# murdock_top_v2.net
KiCad netlist of a schematic drawn in EAGLE
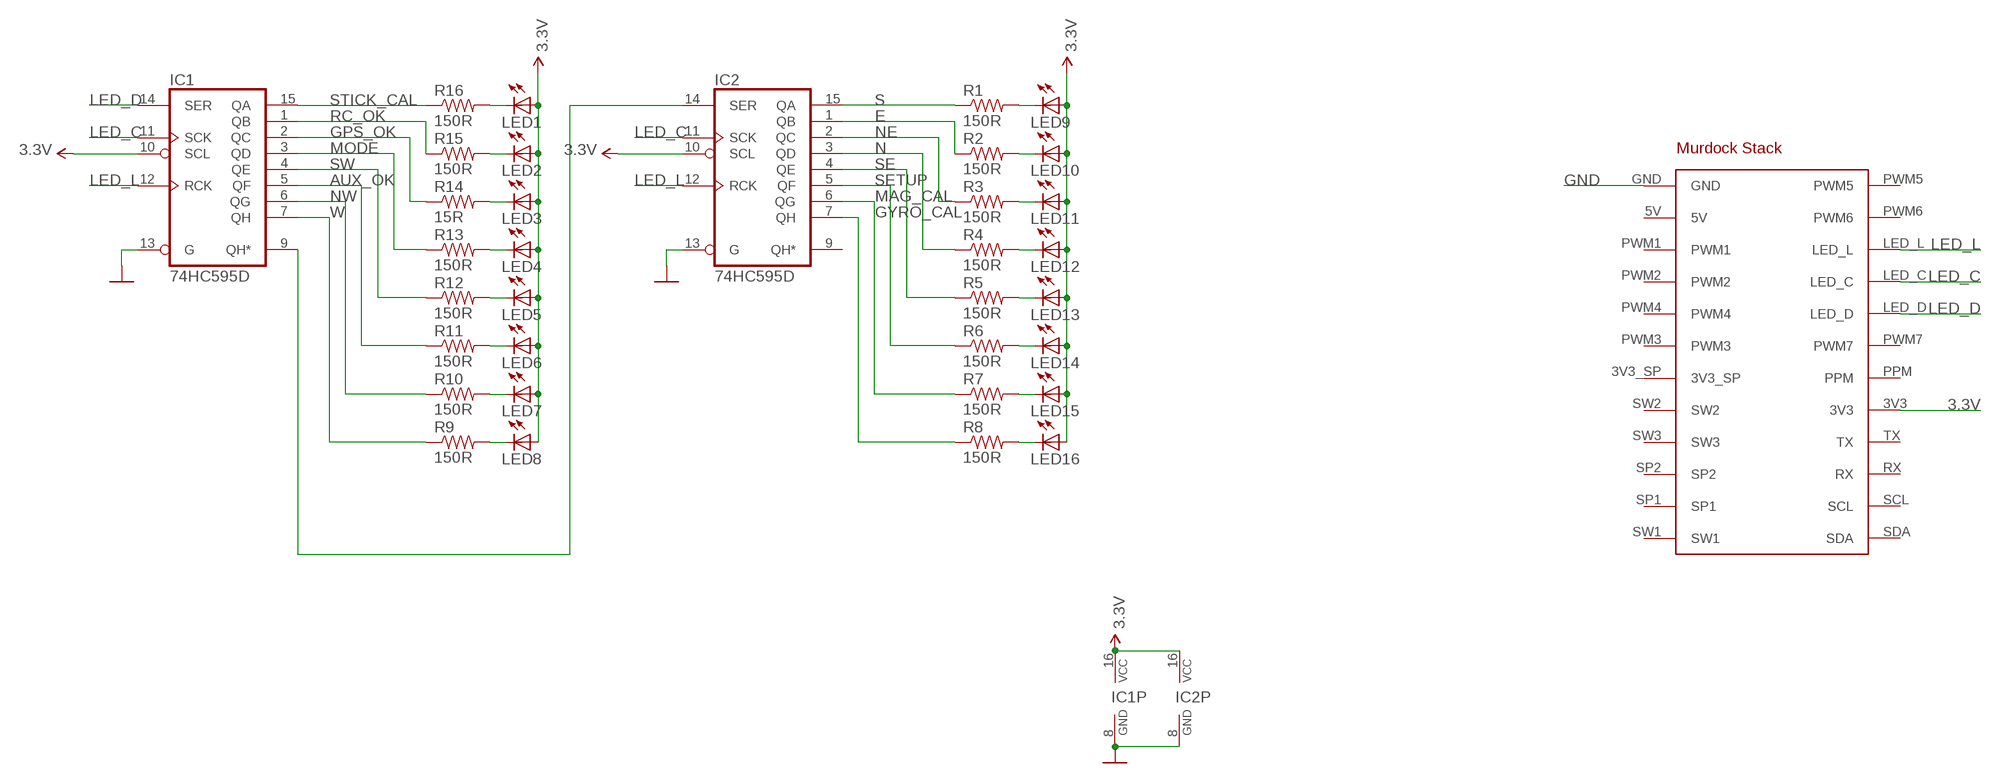
[diagram p0: schematic, sheet 1]

(export (version "E")
  (design (tool "Eeschema 10.0.6"))
  (components
    (comp (ref "IC1")
      (value "74HC595D")
      (footprint "eagle-import:SO16")
      (libsource (lib "eagle-import") (part "74595DHC"))
    )
    (comp (ref "IC2")
      (value "74HC595D")
      (footprint "eagle-import:SO16")
      (libsource (lib "eagle-import") (part "74595DHC"))
    )
    (comp (ref "LED1")
      (value "LGM47K")
      (footprint "eagle-import:LGM47K")
      (libsource (lib "eagle-import") (part "LGM47K"))
    )
    (comp (ref "LED2")
      (value "LGM47K")
      (footprint "eagle-import:LGM47K")
      (libsource (lib "eagle-import") (part "LGM47K"))
    )
    (comp (ref "LED3")
      (value "LGM47K")
      (footprint "eagle-import:LGM47K")
      (libsource (lib "eagle-import") (part "LGM47K"))
    )
    (comp (ref "LED4")
      (value "LGM47K")
      (footprint "eagle-import:LGM47K")
      (libsource (lib "eagle-import") (part "LGM47K"))
    )
    (comp (ref "LED5")
      (value "LGM47K")
      (footprint "eagle-import:LGM47K")
      (libsource (lib "eagle-import") (part "LGM47K"))
    )
    (comp (ref "LED6")
      (value "LGM47K")
      (footprint "eagle-import:LGM47K")
      (libsource (lib "eagle-import") (part "LGM47K"))
    )
    (comp (ref "LED7")
      (value "LGM47K")
      (footprint "eagle-import:LGM47K")
      (libsource (lib "eagle-import") (part "LGM47K"))
    )
    (comp (ref "LED8")
      (value "LGM47K")
      (footprint "eagle-import:LGM47K")
      (libsource (lib "eagle-import") (part "LGM47K"))
    )
    (comp (ref "LED9")
      (value "LGM47K")
      (footprint "eagle-import:LGM47K")
      (libsource (lib "eagle-import") (part "LGM47K"))
    )
    (comp (ref "LED10")
      (value "LGM47K")
      (footprint "eagle-import:LGM47K")
      (libsource (lib "eagle-import") (part "LGM47K"))
    )
    (comp (ref "LED11")
      (value "LGM47K")
      (footprint "eagle-import:LGM47K")
      (libsource (lib "eagle-import") (part "LGM47K"))
    )
    (comp (ref "LED12")
      (value "LGM47K")
      (footprint "eagle-import:LGM47K")
      (libsource (lib "eagle-import") (part "LGM47K"))
    )
    (comp (ref "LED13")
      (value "LGM47K")
      (footprint "eagle-import:LGM47K")
      (libsource (lib "eagle-import") (part "LGM47K"))
    )
    (comp (ref "LED14")
      (value "LGM47K")
      (footprint "eagle-import:LGM47K")
      (libsource (lib "eagle-import") (part "LGM47K"))
    )
    (comp (ref "LED15")
      (value "LGM47K")
      (footprint "eagle-import:LGM47K")
      (libsource (lib "eagle-import") (part "LGM47K"))
    )
    (comp (ref "LED16")
      (value "LGM47K")
      (footprint "eagle-import:LGM47K")
      (libsource (lib "eagle-import") (part "LGM47K"))
    )
    (comp (ref "R1")
      (value "150R")
      (footprint "eagle-import:0402-RES")
      (libsource (lib "eagle-import") (part "RESISTOR0402-RES"))
    )
    (comp (ref "R2")
      (value "150R")
      (footprint "eagle-import:0402-RES")
      (libsource (lib "eagle-import") (part "RESISTOR0402-RES"))
    )
    (comp (ref "R3")
      (value "150R")
      (footprint "eagle-import:0402-RES")
      (libsource (lib "eagle-import") (part "RESISTOR0402-RES"))
    )
    (comp (ref "R4")
      (value "150R")
      (footprint "eagle-import:0402-RES")
      (libsource (lib "eagle-import") (part "RESISTOR0402-RES"))
    )
    (comp (ref "R5")
      (value "150R")
      (footprint "eagle-import:0402-RES")
      (libsource (lib "eagle-import") (part "RESISTOR0402-RES"))
    )
    (comp (ref "R6")
      (value "150R")
      (footprint "eagle-import:0402-RES")
      (libsource (lib "eagle-import") (part "RESISTOR0402-RES"))
    )
    (comp (ref "R7")
      (value "150R")
      (footprint "eagle-import:0402-RES")
      (libsource (lib "eagle-import") (part "RESISTOR0402-RES"))
    )
    (comp (ref "R8")
      (value "150R")
      (footprint "eagle-import:0402-RES")
      (libsource (lib "eagle-import") (part "RESISTOR0402-RES"))
    )
    (comp (ref "R9")
      (value "150R")
      (footprint "eagle-import:0402-RES")
      (libsource (lib "eagle-import") (part "RESISTOR0402-RES"))
    )
    (comp (ref "R10")
      (value "150R")
      (footprint "eagle-import:0402-RES")
      (libsource (lib "eagle-import") (part "RESISTOR0402-RES"))
    )
    (comp (ref "R11")
      (value "150R")
      (footprint "eagle-import:0402-RES")
      (libsource (lib "eagle-import") (part "RESISTOR0402-RES"))
    )
    (comp (ref "R12")
      (value "150R")
      (footprint "eagle-import:0402-RES")
      (libsource (lib "eagle-import") (part "RESISTOR0402-RES"))
    )
    (comp (ref "R13")
      (value "150R")
      (footprint "eagle-import:0402-RES")
      (libsource (lib "eagle-import") (part "RESISTOR0402-RES"))
    )
    (comp (ref "R14")
      (value "15R")
      (footprint "eagle-import:0402-RES")
      (libsource (lib "eagle-import") (part "RESISTOR0402-RES"))
    )
    (comp (ref "R15")
      (value "150R")
      (footprint "eagle-import:0402-RES")
      (libsource (lib "eagle-import") (part "RESISTOR0402-RES"))
    )
    (comp (ref "R16")
      (value "150R")
      (footprint "eagle-import:0402-RES")
      (libsource (lib "eagle-import") (part "RESISTOR0402-RES"))
    )
    (comp (ref "X1")
      (value "MURDOCK_STACK")
      (footprint "eagle-import:MURDOCK_STACK")
      (libsource (lib "eagle-import") (part "MURDOCK_STACK"))
    )
  )
  (nets
    (net (code "1") (name "/AUX_OK") (class "Default")
      (node (ref "IC1") (pin "5") (pinfunction "QF_5") (pintype "tri_state"))
      (node (ref "R11") (pin "1") (pinfunction "1_1") (pintype "passive"))
    )
    (net (code "2") (name "/E") (class "Default")
      (node (ref "IC2") (pin "1") (pinfunction "QB_1") (pintype "tri_state"))
      (node (ref "R2") (pin "1") (pinfunction "1_1") (pintype "passive"))
    )
    (net (code "3") (name "/GPS_OK") (class "Default")
      (node (ref "IC1") (pin "2") (pinfunction "QC_2") (pintype "tri_state"))
      (node (ref "R14") (pin "1") (pinfunction "1_1") (pintype "passive"))
    )
    (net (code "4") (name "/GYRO_CAL") (class "Default")
      (node (ref "IC2") (pin "7") (pinfunction "QH_7") (pintype "tri_state"))
      (node (ref "R8") (pin "1") (pinfunction "1_1") (pintype "passive"))
    )
    (net (code "5") (name "/LED_C") (class "Default")
      (node (ref "IC1") (pin "11") (pinfunction "SCK_11") (pintype "input"))
      (node (ref "IC2") (pin "11") (pinfunction "SCK_11") (pintype "input"))
      (node (ref "X1") (pin "LED_C") (pinfunction "LED_C_LED_C") (pintype "bidirectional"))
    )
    (net (code "6") (name "/LED_D") (class "Default")
      (node (ref "IC1") (pin "14") (pinfunction "SER_14") (pintype "input"))
      (node (ref "X1") (pin "LED_D") (pinfunction "LED_D_LED_D") (pintype "bidirectional"))
    )
    (net (code "7") (name "/LED_L") (class "Default")
      (node (ref "IC1") (pin "12") (pinfunction "RCK_12") (pintype "input"))
      (node (ref "IC2") (pin "12") (pinfunction "RCK_12") (pintype "input"))
      (node (ref "X1") (pin "LED_L") (pinfunction "LED_L_LED_L") (pintype "bidirectional"))
    )
    (net (code "8") (name "/MAG_CAL") (class "Default")
      (node (ref "IC2") (pin "6") (pinfunction "QG_6") (pintype "tri_state"))
      (node (ref "R7") (pin "1") (pinfunction "1_1") (pintype "passive"))
    )
    (net (code "9") (name "/MODE") (class "Default")
      (node (ref "IC1") (pin "3") (pinfunction "QD_3") (pintype "tri_state"))
      (node (ref "R13") (pin "1") (pinfunction "1_1") (pintype "passive"))
    )
    (net (code "10") (name "/N") (class "Default")
      (node (ref "IC2") (pin "3") (pinfunction "QD_3") (pintype "tri_state"))
      (node (ref "R4") (pin "1") (pinfunction "1_1") (pintype "passive"))
    )
    (net (code "11") (name "/NE") (class "Default")
      (node (ref "IC2") (pin "2") (pinfunction "QC_2") (pintype "tri_state"))
      (node (ref "R3") (pin "1") (pinfunction "1_1") (pintype "passive"))
    )
    (net (code "12") (name "/NW") (class "Default")
      (node (ref "IC1") (pin "6") (pinfunction "QG_6") (pintype "tri_state"))
      (node (ref "R10") (pin "1") (pinfunction "1_1") (pintype "passive"))
    )
    (net (code "13") (name "/RC_OK") (class "Default")
      (node (ref "IC1") (pin "1") (pinfunction "QB_1") (pintype "tri_state"))
      (node (ref "R15") (pin "1") (pinfunction "1_1") (pintype "passive"))
    )
    (net (code "14") (name "/S") (class "Default")
      (node (ref "IC2") (pin "15") (pinfunction "QA_15") (pintype "tri_state"))
      (node (ref "R1") (pin "1") (pinfunction "1_1") (pintype "passive"))
    )
    (net (code "15") (name "/SE") (class "Default")
      (node (ref "IC2") (pin "4") (pinfunction "QE_4") (pintype "tri_state"))
      (node (ref "R5") (pin "1") (pinfunction "1_1") (pintype "passive"))
    )
    (net (code "16") (name "/SETUP") (class "Default")
      (node (ref "IC2") (pin "5") (pinfunction "QF_5") (pintype "tri_state"))
      (node (ref "R6") (pin "1") (pinfunction "1_1") (pintype "passive"))
    )
    (net (code "17") (name "/STICK_CAL") (class "Default")
      (node (ref "IC1") (pin "15") (pinfunction "QA_15") (pintype "tri_state"))
      (node (ref "R16") (pin "1") (pinfunction "1_1") (pintype "passive"))
    )
    (net (code "18") (name "/SW") (class "Default")
      (node (ref "IC1") (pin "4") (pinfunction "QE_4") (pintype "tri_state"))
      (node (ref "R12") (pin "1") (pinfunction "1_1") (pintype "passive"))
    )
    (net (code "19") (name "/W") (class "Default")
      (node (ref "IC1") (pin "7") (pinfunction "QH_7") (pintype "tri_state"))
      (node (ref "R9") (pin "1") (pinfunction "1_1") (pintype "passive"))
    )
    (net (code "20") (name "3.3V") (class "Default")
      (node (ref "IC1") (pin "10") (pinfunction "SCL_10") (pintype "input"))
      (node (ref "IC1") (pin "16") (pinfunction "VCC_16") (pintype "power_in"))
      (node (ref "IC2") (pin "10") (pinfunction "SCL_10") (pintype "input"))
      (node (ref "IC2") (pin "16") (pinfunction "VCC_16") (pintype "power_in"))
      (node (ref "LED1") (pin "A") (pinfunction "A_A") (pintype "passive"))
      (node (ref "LED10") (pin "A") (pinfunction "A_A") (pintype "passive"))
      (node (ref "LED11") (pin "A") (pinfunction "A_A") (pintype "passive"))
      (node (ref "LED12") (pin "A") (pinfunction "A_A") (pintype "passive"))
      (node (ref "LED13") (pin "A") (pinfunction "A_A") (pintype "passive"))
      (node (ref "LED14") (pin "A") (pinfunction "A_A") (pintype "passive"))
      (node (ref "LED15") (pin "A") (pinfunction "A_A") (pintype "passive"))
      (node (ref "LED16") (pin "A") (pinfunction "A_A") (pintype "passive"))
      (node (ref "LED2") (pin "A") (pinfunction "A_A") (pintype "passive"))
      (node (ref "LED3") (pin "A") (pinfunction "A_A") (pintype "passive"))
      (node (ref "LED4") (pin "A") (pinfunction "A_A") (pintype "passive"))
      (node (ref "LED5") (pin "A") (pinfunction "A_A") (pintype "passive"))
      (node (ref "LED6") (pin "A") (pinfunction "A_A") (pintype "passive"))
      (node (ref "LED7") (pin "A") (pinfunction "A_A") (pintype "passive"))
      (node (ref "LED8") (pin "A") (pinfunction "A_A") (pintype "passive"))
      (node (ref "LED9") (pin "A") (pinfunction "A_A") (pintype "passive"))
      (node (ref "X1") (pin "3V3") (pinfunction "3V3_3V3") (pintype "bidirectional"))
    )
    (net (code "21") (name "GND") (class "Default")
      (node (ref "IC1") (pin "13") (pinfunction "G_13") (pintype "input"))
      (node (ref "IC1") (pin "8") (pinfunction "GND_8") (pintype "power_in"))
      (node (ref "IC2") (pin "13") (pinfunction "G_13") (pintype "input"))
      (node (ref "IC2") (pin "8") (pinfunction "GND_8") (pintype "power_in"))
      (node (ref "X1") (pin "GND") (pinfunction "GND_GND") (pintype "bidirectional"))
    )
    (net (code "22") (name "Net-(IC1A-QH*)") (class "Default")
      (node (ref "IC1") (pin "9") (pinfunction "QH*_9") (pintype "tri_state"))
      (node (ref "IC2") (pin "14") (pinfunction "SER_14") (pintype "input"))
    )
    (net (code "23") (name "Net-(LED1-C)") (class "Default")
      (node (ref "LED1") (pin "K") (pinfunction "C_K") (pintype "passive"))
      (node (ref "R16") (pin "2") (pinfunction "2_2") (pintype "passive"))
    )
    (net (code "24") (name "Net-(LED2-C)") (class "Default")
      (node (ref "LED2") (pin "K") (pinfunction "C_K") (pintype "passive"))
      (node (ref "R15") (pin "2") (pinfunction "2_2") (pintype "passive"))
    )
    (net (code "25") (name "Net-(LED3-C)") (class "Default")
      (node (ref "LED3") (pin "K") (pinfunction "C_K") (pintype "passive"))
      (node (ref "R14") (pin "2") (pinfunction "2_2") (pintype "passive"))
    )
    (net (code "26") (name "Net-(LED4-C)") (class "Default")
      (node (ref "LED4") (pin "K") (pinfunction "C_K") (pintype "passive"))
      (node (ref "R13") (pin "2") (pinfunction "2_2") (pintype "passive"))
    )
    (net (code "27") (name "Net-(LED5-C)") (class "Default")
      (node (ref "LED5") (pin "K") (pinfunction "C_K") (pintype "passive"))
      (node (ref "R12") (pin "2") (pinfunction "2_2") (pintype "passive"))
    )
    (net (code "28") (name "Net-(LED6-C)") (class "Default")
      (node (ref "LED6") (pin "K") (pinfunction "C_K") (pintype "passive"))
      (node (ref "R11") (pin "2") (pinfunction "2_2") (pintype "passive"))
    )
    (net (code "29") (name "Net-(LED7-C)") (class "Default")
      (node (ref "LED7") (pin "K") (pinfunction "C_K") (pintype "passive"))
      (node (ref "R10") (pin "2") (pinfunction "2_2") (pintype "passive"))
    )
    (net (code "30") (name "Net-(LED8-C)") (class "Default")
      (node (ref "LED8") (pin "K") (pinfunction "C_K") (pintype "passive"))
      (node (ref "R9") (pin "2") (pinfunction "2_2") (pintype "passive"))
    )
    (net (code "31") (name "Net-(LED9-C)") (class "Default")
      (node (ref "LED9") (pin "K") (pinfunction "C_K") (pintype "passive"))
      (node (ref "R1") (pin "2") (pinfunction "2_2") (pintype "passive"))
    )
    (net (code "32") (name "Net-(LED10-C)") (class "Default")
      (node (ref "LED10") (pin "K") (pinfunction "C_K") (pintype "passive"))
      (node (ref "R2") (pin "2") (pinfunction "2_2") (pintype "passive"))
    )
    (net (code "33") (name "Net-(LED11-C)") (class "Default")
      (node (ref "LED11") (pin "K") (pinfunction "C_K") (pintype "passive"))
      (node (ref "R3") (pin "2") (pinfunction "2_2") (pintype "passive"))
    )
    (net (code "34") (name "Net-(LED12-C)") (class "Default")
      (node (ref "LED12") (pin "K") (pinfunction "C_K") (pintype "passive"))
      (node (ref "R4") (pin "2") (pinfunction "2_2") (pintype "passive"))
    )
    (net (code "35") (name "Net-(LED13-C)") (class "Default")
      (node (ref "LED13") (pin "K") (pinfunction "C_K") (pintype "passive"))
      (node (ref "R5") (pin "2") (pinfunction "2_2") (pintype "passive"))
    )
    (net (code "36") (name "Net-(LED14-C)") (class "Default")
      (node (ref "LED14") (pin "K") (pinfunction "C_K") (pintype "passive"))
      (node (ref "R6") (pin "2") (pinfunction "2_2") (pintype "passive"))
    )
    (net (code "37") (name "Net-(LED15-C)") (class "Default")
      (node (ref "LED15") (pin "K") (pinfunction "C_K") (pintype "passive"))
      (node (ref "R7") (pin "2") (pinfunction "2_2") (pintype "passive"))
    )
    (net (code "38") (name "Net-(LED16-C)") (class "Default")
      (node (ref "LED16") (pin "K") (pinfunction "C_K") (pintype "passive"))
      (node (ref "R8") (pin "2") (pinfunction "2_2") (pintype "passive"))
    )
    (net (code "39") (name "unconnected-(IC2A-QH*-Pad9)") (class "Default")
      (node (ref "IC2") (pin "9") (pinfunction "QH*_9") (pintype "tri_state"))
    )
    (net (code "40") (name "unconnected-(X1-Pad3V3_SP)") (class "Default")
      (node (ref "X1") (pin "3V3_SP") (pinfunction "3V3_SP_3V3_SP") (pintype "bidirectional"))
    )
    (net (code "41") (name "unconnected-(X1-Pad5V)") (class "Default")
      (node (ref "X1") (pin "5V") (pinfunction "5V_5V") (pintype "bidirectional"))
    )
    (net (code "42") (name "unconnected-(X1-PadPPM)") (class "Default")
      (node (ref "X1") (pin "PPM") (pinfunction "PPM_PPM") (pintype "bidirectional"))
    )
    (net (code "43") (name "unconnected-(X1-PadPWM1)") (class "Default")
      (node (ref "X1") (pin "PWM1") (pinfunction "PWM1_PWM1") (pintype "bidirectional"))
    )
    (net (code "44") (name "unconnected-(X1-PadPWM2)") (class "Default")
      (node (ref "X1") (pin "PWM2") (pinfunction "PWM2_PWM2") (pintype "bidirectional"))
    )
    (net (code "45") (name "unconnected-(X1-PadPWM3)") (class "Default")
      (node (ref "X1") (pin "PWM3") (pinfunction "PWM3_PWM3") (pintype "bidirectional"))
    )
    (net (code "46") (name "unconnected-(X1-PadPWM4)") (class "Default")
      (node (ref "X1") (pin "PWM4") (pinfunction "PWM4_PWM4") (pintype "bidirectional"))
    )
    (net (code "47") (name "unconnected-(X1-PadPWM5)") (class "Default")
      (node (ref "X1") (pin "PWM5") (pinfunction "PWM5_PWM5") (pintype "bidirectional"))
    )
    (net (code "48") (name "unconnected-(X1-PadPWM6)") (class "Default")
      (node (ref "X1") (pin "PWM6") (pinfunction "PWM6_PWM6") (pintype "bidirectional"))
    )
    (net (code "49") (name "unconnected-(X1-PadPWM7)") (class "Default")
      (node (ref "X1") (pin "PWM7") (pinfunction "PWM7_PWM7") (pintype "bidirectional"))
    )
    (net (code "50") (name "unconnected-(X1-PadRX)") (class "Default")
      (node (ref "X1") (pin "RX") (pinfunction "RX_RX") (pintype "bidirectional"))
    )
    (net (code "51") (name "unconnected-(X1-PadSCL)") (class "Default")
      (node (ref "X1") (pin "SCL") (pinfunction "SCL_SCL") (pintype "bidirectional"))
    )
    (net (code "52") (name "unconnected-(X1-PadSDA)") (class "Default")
      (node (ref "X1") (pin "SDA") (pinfunction "SDA_SDA") (pintype "bidirectional"))
    )
    (net (code "53") (name "unconnected-(X1-PadSP1)") (class "Default")
      (node (ref "X1") (pin "SP1") (pinfunction "SP1_SP1") (pintype "bidirectional"))
    )
    (net (code "54") (name "unconnected-(X1-PadSP2)") (class "Default")
      (node (ref "X1") (pin "SP2") (pinfunction "SP2_SP2") (pintype "bidirectional"))
    )
    (net (code "55") (name "unconnected-(X1-PadSW1)") (class "Default")
      (node (ref "X1") (pin "SW1") (pinfunction "SW1_SW1") (pintype "bidirectional"))
    )
    (net (code "56") (name "unconnected-(X1-PadSW2)") (class "Default")
      (node (ref "X1") (pin "SW2") (pinfunction "SW2_SW2") (pintype "bidirectional"))
    )
    (net (code "57") (name "unconnected-(X1-PadSW3)") (class "Default")
      (node (ref "X1") (pin "SW3") (pinfunction "SW3_SW3") (pintype "bidirectional"))
    )
    (net (code "58") (name "unconnected-(X1-PadTX)") (class "Default")
      (node (ref "X1") (pin "TX") (pinfunction "TX_TX") (pintype "bidirectional"))
    )
  )
)
